# MAIN.net
KiCad netlist of a schematic drawn in Altium Designer
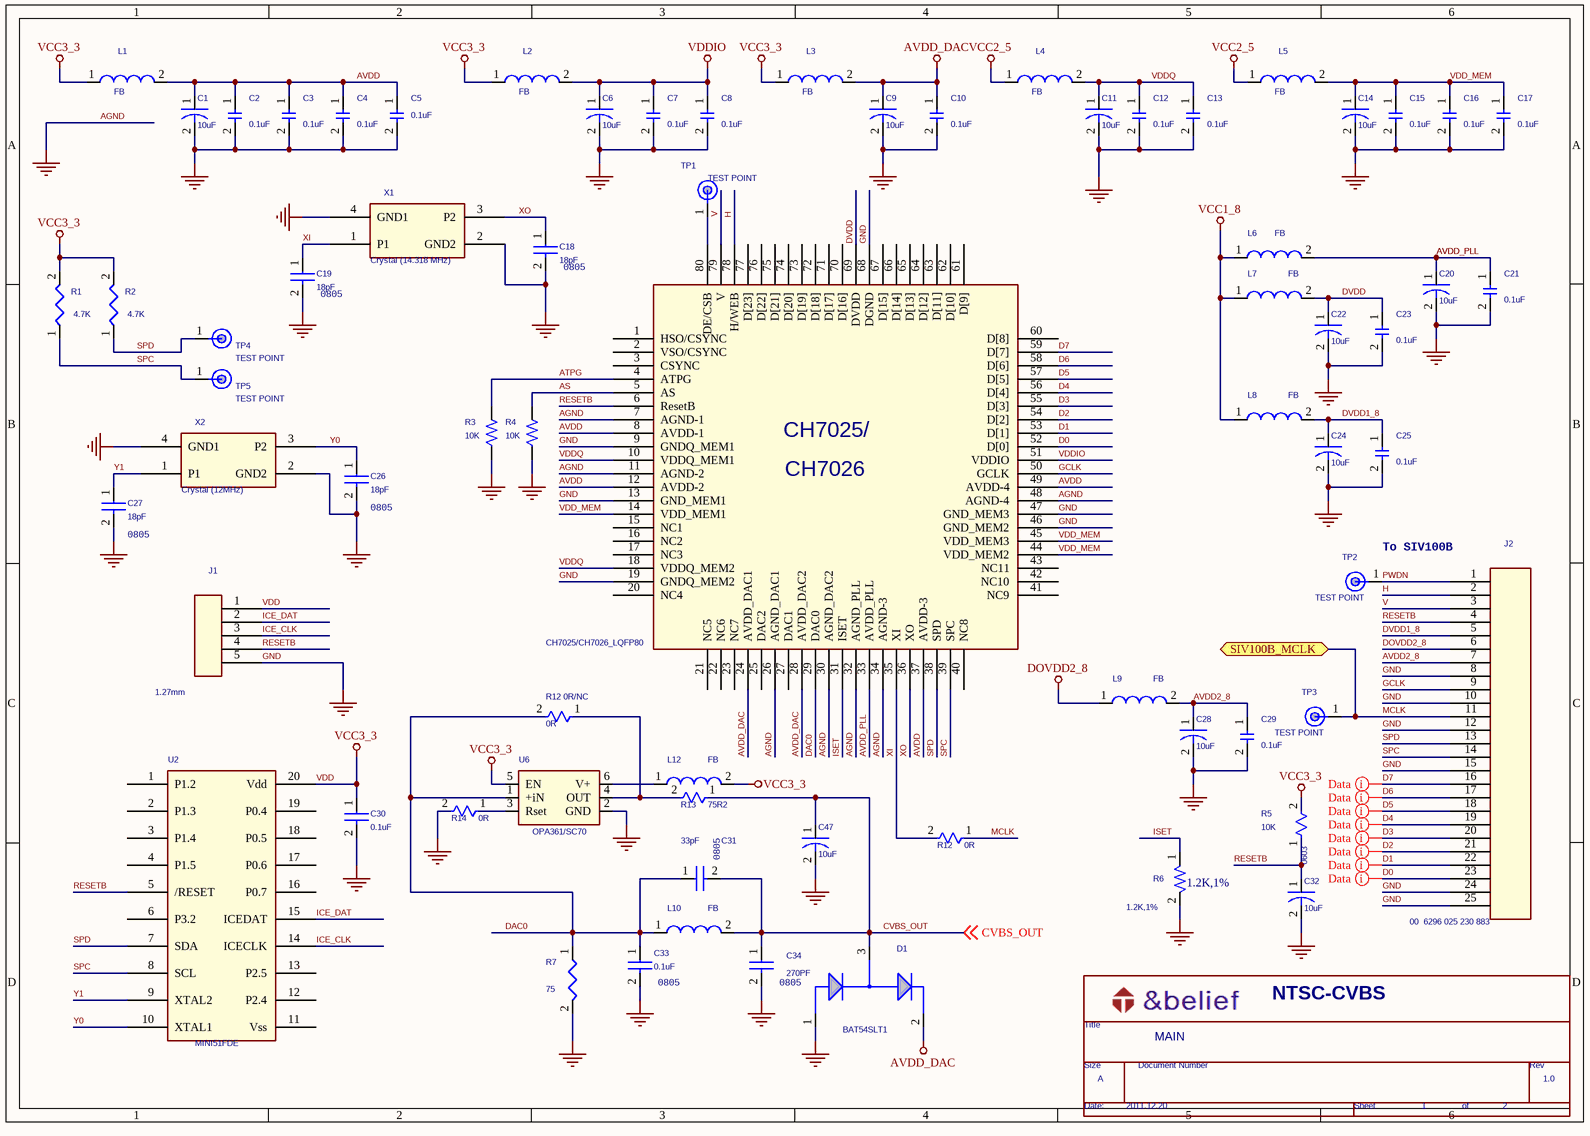
[diagram p0: MAIN.SchDoc]

(export (version "E")
  (design (tool "Eeschema 10.0.6"))
  (components
    (comp (ref "C1")
      (value "10uF")
      (footprint "CAPC1608X90N")
      (description "CAP - 10uF 16V TE Tant")
      (fields (field (name "MANUFACTURER PART NUM") "T491B106M016AS") (field (name "MANUFACTURER") "Kemet"))
      (libsource (lib "*") (part "PCAP_0"))
    )
    (comp (ref "C2")
      (value "0.1uF")
      (footprint "CAPC1005X55N")
      (fields (field (name "VOLTAGE") "CMAX"))
      (libsource (lib "*") (part "C_0"))
    )
    (comp (ref "C3")
      (value "0.1uF")
      (footprint "CAPC1005X55N")
      (fields (field (name "VOLTAGE") "CMAX"))
      (libsource (lib "*") (part "C_0"))
    )
    (comp (ref "C4")
      (value "0.1uF")
      (footprint "CAPC1005X55N")
      (fields (field (name "VOLTAGE") "CMAX"))
      (libsource (lib "*") (part "C_0"))
    )
    (comp (ref "C5")
      (value "0.1uF")
      (footprint "CAPC1005X55N")
      (fields (field (name "VOLTAGE") "CMAX"))
      (libsource (lib "*") (part "C_0"))
    )
    (comp (ref "C6")
      (value "10uF")
      (footprint "CAPC1608X90N")
      (description "CAP - 10uF 16V TE Tant")
      (fields (field (name "MANUFACTURER PART NUM") "T491B106M016AS") (field (name "MANUFACTURER") "Kemet"))
      (libsource (lib "*") (part "PCAP_0"))
    )
    (comp (ref "C7")
      (value "0.1uF")
      (footprint "CAPC1005X55N")
      (fields (field (name "VOLTAGE") "CMAX"))
      (libsource (lib "*") (part "C_0"))
    )
    (comp (ref "C8")
      (value "0.1uF")
      (footprint "CAPC1005X55N")
      (fields (field (name "VOLTAGE") "CMAX"))
      (libsource (lib "*") (part "C_0"))
    )
    (comp (ref "C9")
      (value "10uF")
      (footprint "CAPC1608X90N")
      (description "CAP - 10uF 16V TE Tant")
      (fields (field (name "MANUFACTURER PART NUM") "T491B106M016AS") (field (name "MANUFACTURER") "Kemet"))
      (libsource (lib "*") (part "PCAP_0"))
    )
    (comp (ref "C10")
      (value "0.1uF")
      (footprint "CAPC1005X55N")
      (fields (field (name "VOLTAGE") "CMAX"))
      (libsource (lib "*") (part "C_0"))
    )
    (comp (ref "C11")
      (value "10uF")
      (footprint "CAPC1608X90N")
      (description "CAP - 10uF 16V TE Tant")
      (fields (field (name "MANUFACTURER PART NUM") "T491B106M016AS") (field (name "MANUFACTURER") "Kemet"))
      (libsource (lib "*") (part "PCAP_0"))
    )
    (comp (ref "C12")
      (value "0.1uF")
      (footprint "CAPC1005X55N")
      (fields (field (name "VOLTAGE") "CMAX"))
      (libsource (lib "*") (part "C_0"))
    )
    (comp (ref "C13")
      (value "0.1uF")
      (footprint "CAPC1005X55N")
      (fields (field (name "VOLTAGE") "CMAX"))
      (libsource (lib "*") (part "C_0"))
    )
    (comp (ref "C14")
      (value "10uF")
      (footprint "CAPC1608X90N")
      (description "CAP - 10uF 16V TE Tant")
      (fields (field (name "MANUFACTURER PART NUM") "T491B106M016AS") (field (name "MANUFACTURER") "Kemet"))
      (libsource (lib "*") (part "PCAP_0"))
    )
    (comp (ref "C15")
      (value "0.1uF")
      (footprint "CAPC1005X55N")
      (fields (field (name "VOLTAGE") "CMAX"))
      (libsource (lib "*") (part "C_0"))
    )
    (comp (ref "C16")
      (value "0.1uF")
      (footprint "CAPC1005X55N")
      (fields (field (name "VOLTAGE") "CMAX"))
      (libsource (lib "*") (part "C_0"))
    )
    (comp (ref "C17")
      (value "0.1uF")
      (footprint "CAPC1005X55N")
      (fields (field (name "VOLTAGE") "CMAX"))
      (libsource (lib "*") (part "C_0"))
    )
    (comp (ref "C18")
      (value "18pF")
      (footprint "CAPC1005X55N")
      (fields (field (name "PART SHAPE") "0805"))
      (libsource (lib "*") (part "CAP"))
    )
    (comp (ref "C19")
      (value "18pF")
      (footprint "CAPC1005X55N")
      (fields (field (name "PART SHAPE") "0805"))
      (libsource (lib "*") (part "CAP"))
    )
    (comp (ref "C20")
      (value "10uF")
      (footprint "CAPC1608X90N")
      (description "CAP - 10uF 16V TE Tant")
      (fields (field (name "MANUFACTURER PART NUM") "T491B106M016AS") (field (name "MANUFACTURER") "Kemet"))
      (libsource (lib "*") (part "PCAP_0"))
    )
    (comp (ref "C21")
      (value "0.1uF")
      (footprint "CAPC1005X55N")
      (fields (field (name "VOLTAGE") "CMAX"))
      (libsource (lib "*") (part "C_0"))
    )
    (comp (ref "C22")
      (value "10uF")
      (footprint "CAPC1608X90N")
      (description "CAP - 10uF 16V TE Tant")
      (fields (field (name "MANUFATURER PART NUMBER") "T491B106M016AS") (field (name "MANUFACTURER") "Kemet"))
      (libsource (lib "*") (part "PCAP_0"))
    )
    (comp (ref "C23")
      (value "0.1uF")
      (footprint "CAPC1005X55N")
      (fields (field (name "VOLTAGE") "CMAX"))
      (libsource (lib "*") (part "C_0"))
    )
    (comp (ref "C24")
      (value "10uF")
      (footprint "CAPC1608X90N")
      (description "CAP - 10uF 16V TE Tant")
      (fields (field (name "MANUFACTURER PART NUM") "T491B106M016AS") (field (name "MANUFACTURER") "Kemet"))
      (libsource (lib "*") (part "PCAP_0"))
    )
    (comp (ref "C25")
      (value "0.1uF")
      (footprint "CAPC1005X55N")
      (fields (field (name "VOLTAGE") "CMAX"))
      (libsource (lib "*") (part "C_0"))
    )
    (comp (ref "C26")
      (value "18pF")
      (footprint "CAPC1005X55N")
      (fields (field (name "PART SHAPE") "0805"))
      (libsource (lib "*") (part "CAP"))
    )
    (comp (ref "C27")
      (value "18pF")
      (footprint "CAPC1005X55N")
      (fields (field (name "PART SHAPE") "0805"))
      (libsource (lib "*") (part "CAP"))
    )
    (comp (ref "C28")
      (value "10uF")
      (footprint "CAPC1608X90N")
      (description "CAP - 10uF 16V TE Tant")
      (fields (field (name "MANUFATURER PART NUMBER") "T491B106M016AS") (field (name "MANUFACTURER") "Kemet"))
      (libsource (lib "*") (part "PCAP_0"))
    )
    (comp (ref "C29")
      (value "0.1uF")
      (footprint "CAPC1005X55N")
      (fields (field (name "VOLTAGE") "CMAX"))
      (libsource (lib "*") (part "C_0"))
    )
    (comp (ref "C30") (value "0.1uF") (footprint "CAPC1005X55N") (libsource (lib "*") (part "CAP NP_3")))
    (comp (ref "C31")
      (value "33pF")
      (footprint "CAPC1005X55N")
      (fields (field (name "PART SHAPE") "0805"))
      (libsource (lib "*") (part "CAP"))
    )
    (comp (ref "C32")
      (value "10uF")
      (footprint "CAPC1608X90N")
      (description "CAP - 10uF 16V TE Tant")
      (fields (field (name "MANUFATURER PART NUMBER") "T491B106M016AS") (field (name "MANUFACTURER") "Kemet"))
      (libsource (lib "*") (part "PCAP_0"))
    )
    (comp (ref "C33")
      (value "0.1uF")
      (footprint "CAPC1005X55N")
      (fields (field (name "PART SHAPE") "0805"))
      (libsource (lib "*") (part "CAP"))
    )
    (comp (ref "C34")
      (value "270PF")
      (footprint "CAPC1005X55N")
      (fields (field (name "PART SHAPE") "0805"))
      (libsource (lib "*") (part "CAP"))
    )
    (comp (ref "C47")
      (value "10uF")
      (footprint "CAPC1608X90N")
      (description "CAP - 10uF 16V TE Tant")
      (fields (field (name "MANUFATURER PART NUMBER") "T491B106M016AS") (field (name "MANUFACTURER") "Kemet"))
      (libsource (lib "*") (part "PCAP_0"))
    )
    (comp (ref "D1")
      (value "BAT54SLT1")
      (footprint "SOT23-3")
      (libsource (lib "*") (part "DIODE DUAL SERIES SOT23"))
    )
    (comp (ref "J1") (value "1.27mm") (footprint "JP 1.27mm") (libsource (lib "*") (part "CON5_Dup1")))
    (comp (ref "J2")
      (value "00  6296 025 230 883")
      (footprint "FPC ASSY 0.3MM")
      (libsource (lib "*") (part "CON25"))
    )
    (comp (ref "L1") (value "FB") (footprint "INDC1005N") (libsource (lib "*") (part "INDUCTOR")))
    (comp (ref "L2") (value "FB") (footprint "INDC1005N") (libsource (lib "*") (part "INDUCTOR")))
    (comp (ref "L3") (value "FB") (footprint "INDC1005N") (libsource (lib "*") (part "INDUCTOR")))
    (comp (ref "L4") (value "FB") (footprint "INDC1005N") (libsource (lib "*") (part "INDUCTOR")))
    (comp (ref "L5") (value "FB") (footprint "INDC1005N") (libsource (lib "*") (part "INDUCTOR")))
    (comp (ref "L6") (value "FB") (footprint "INDC1005N") (libsource (lib "*") (part "INDUCTOR")))
    (comp (ref "L7") (value "FB") (footprint "INDC1005N") (libsource (lib "*") (part "INDUCTOR")))
    (comp (ref "L8") (value "FB") (footprint "INDC1005N") (libsource (lib "*") (part "INDUCTOR")))
    (comp (ref "L9") (value "FB") (footprint "INDC1005N") (libsource (lib "*") (part "INDUCTOR")))
    (comp (ref "L10") (value "FB") (footprint "INDC1608N") (libsource (lib "*") (part "INDUCTOR")))
    (comp (ref "L12") (value "FB") (footprint "INDC1005N") (libsource (lib "*") (part "INDUCTOR")))
    (comp (ref "R1") (value "4.7K") (footprint "RESC1005X40N") (libsource (lib "*") (part "RESISTOR")))
    (comp (ref "R2") (value "4.7K") (footprint "RESC1005X40N") (libsource (lib "*") (part "RESISTOR")))
    (comp (ref "R3")
      (value "10K")
      (footprint "RESC1005X40N")
      (fields (field (name "POWER") "RMAX") (field (name "VOLTAGE") "RVMAX"))
      (libsource (lib "*") (part "R"))
    )
    (comp (ref "R4")
      (value "10K")
      (footprint "RESC1005X40N")
      (fields (field (name "POWER") "RMAX") (field (name "VOLTAGE") "RVMAX"))
      (libsource (lib "*") (part "R"))
    )
    (comp (ref "R5")
      (value "10K")
      (footprint "RESC1005X40N")
      (description "0R,1/10W,5%,0603")
      (fields (field (name "TOLERANCE") "∮5%") (field (name "SIZE") "0603"))
      (libsource (lib "*") (part "0R,1/10W,5%,0603_9"))
    )
    (comp (ref "R6")
      (value "1.2K,1%")
      (footprint "RESC1005X40N")
      (fields
        (field (name "POWER") "RMAX")
        (field (name "VOLTAGE") "RVMAX")
        (field (name "ALTIUM_VALUE") "1.2K,1%")
      )
      (libsource (lib "*") (part "R_4"))
    )
    (comp (ref "R7") (value "75") (footprint "RESC1005X40N") (libsource (lib "*") (part "RESISTOR")))
    (comp (ref "R12")
      (value "0R")
      (footprint "RESC1005X40N")
      (description "0R,1/10W,5%,0603")
      (fields (field (name "TOLERANCE") "∮5%"))
      (libsource (lib "*") (part "0R,1/10W,5%,0603_9"))
    )
    (comp (ref "R12 0R/NC")
      (value "0R")
      (footprint "RESC1005X40N")
      (description "0R,1/10W,5%,0603")
      (fields (field (name "TOLERANCE") "∮5%"))
      (libsource (lib "*") (part "0R,1/10W,5%,0603_9"))
    )
    (comp (ref "R13")
      (value "75R2")
      (footprint "RESC1005X40N")
      (description "0R,1/10W,5%,0603")
      (fields (field (name "TOLERANCE") "∮5%"))
      (libsource (lib "*") (part "0R,1/10W,5%,0603_9"))
    )
    (comp (ref "R14")
      (value "0R")
      (footprint "RESC1005X40N")
      (description "0R,1/10W,5%,0603")
      (fields (field (name "TOLERANCE") "∮5%"))
      (libsource (lib "*") (part "0R,1/10W,5%,0603_9"))
    )
    (comp (ref "TP1") (value "TEST POINT") (footprint "TP-R20") (libsource (lib "*") (part "Test Point_0")))
    (comp (ref "TP2") (value "TEST POINT") (footprint "TP-R20") (libsource (lib "*") (part "Test Point_1")))
    (comp (ref "TP3") (value "TEST POINT") (footprint "TP-R20") (libsource (lib "*") (part "Test Point_2")))
    (comp (ref "TP4") (value "TEST POINT") (footprint "TP-R20") (libsource (lib "*") (part "Test Point_0")))
    (comp (ref "TP5") (value "TEST POINT") (footprint "TP-R20") (libsource (lib "*") (part "Test Point_0")))
    (comp (ref "U1")
      (value "CH7025/CH7026_LQFP80")
      (footprint "TQFP80_N")
      (libsource (lib "*") (part "CH7025_LQFP80_0"))
    )
    (comp (ref "U2")
      (value "MINI51FDE")
      (footprint "TSSOP65P640X120-20N")
      (libsource (lib "*") (part "IC TvDecoder TI TVP5150 QFP32_2"))
    )
    (comp (ref "U6")
      (value "OPA361/SC70")
      (footprint "SC07")
      (libsource (lib "*") (part "IC DC/DC RT8258 SOT26_0"))
    )
    (comp (ref "X1")
      (value "Crystal (14.318 MHz)")
      (footprint "XTAL-4pin-3225")
      (libsource (lib "*") (part "535-9118-1-ND_0"))
    )
    (comp (ref "X2")
      (value "Crystal (12MHz)")
      (footprint "XTAL-4pin-3225")
      (libsource (lib "*") (part "535-9118-1-ND_1"))
    )
  )
  (nets
    (net (code "1") (name "/AS") (class "Default")
      (node (ref "R4") (pin "2") (pinfunction "2_2") (pintype "passive"))
      (node (ref "U1") (pin "5") (pinfunction "AS_5") (pintype "passive"))
    )
    (net (code "2") (name "/ATPG") (class "Default")
      (node (ref "R3") (pin "2") (pinfunction "2_2") (pintype "passive"))
      (node (ref "U1") (pin "4") (pinfunction "ATPG_4") (pintype "passive"))
    )
    (net (code "3") (name "/AVDD") (class "Default")
      (node (ref "C1") (pin "1") (pinfunction "1_1") (pintype "passive"))
      (node (ref "C2") (pin "1") (pinfunction "1_1") (pintype "passive"))
      (node (ref "C3") (pin "1") (pinfunction "1_1") (pintype "passive"))
      (node (ref "C4") (pin "1") (pinfunction "1_1") (pintype "passive"))
      (node (ref "C5") (pin "1") (pinfunction "1_1") (pintype "passive"))
      (node (ref "L1") (pin "2") (pinfunction "2_2") (pintype "passive"))
      (node (ref "U1") (pin "12") (pinfunction "AVDD-2_12") (pintype "passive"))
      (node (ref "U1") (pin "37") (pinfunction "AVDD-3_37") (pintype "passive"))
      (node (ref "U1") (pin "49") (pinfunction "AVDD-4_49") (pintype "passive"))
      (node (ref "U1") (pin "8") (pinfunction "AVDD-1_8") (pintype "passive"))
    )
    (net (code "4") (name "/AVDD2_8") (class "Default")
      (node (ref "C28") (pin "1") (pinfunction "1_1") (pintype "passive"))
      (node (ref "C29") (pin "1") (pinfunction "1_1") (pintype "passive"))
      (node (ref "J2") (pin "7") (pinfunction "7_7") (pintype "passive"))
      (node (ref "L9") (pin "2") (pinfunction "2_2") (pintype "passive"))
    )
    (net (code "5") (name "/AVDD_PLL") (class "Default")
      (node (ref "C20") (pin "1") (pinfunction "1_1") (pintype "passive"))
      (node (ref "C21") (pin "1") (pinfunction "1_1") (pintype "passive"))
      (node (ref "L6") (pin "2") (pinfunction "2_2") (pintype "passive"))
      (node (ref "U1") (pin "33") (pinfunction "AVDD_PLL_33") (pintype "passive"))
    )
    (net (code "6") (name "/D0") (class "Default")
      (node (ref "J2") (pin "23") (pinfunction "23_23") (pintype "passive"))
      (node (ref "U1") (pin "52") (pinfunction "D[0]_52") (pintype "passive"))
    )
    (net (code "7") (name "/D1") (class "Default")
      (node (ref "J2") (pin "22") (pinfunction "22_22") (pintype "passive"))
      (node (ref "U1") (pin "53") (pinfunction "D[1]_53") (pintype "passive"))
    )
    (net (code "8") (name "/D2") (class "Default")
      (node (ref "J2") (pin "21") (pinfunction "21_21") (pintype "passive"))
      (node (ref "U1") (pin "54") (pinfunction "D[2]_54") (pintype "passive"))
    )
    (net (code "9") (name "/D3") (class "Default")
      (node (ref "J2") (pin "20") (pinfunction "20_20") (pintype "passive"))
      (node (ref "U1") (pin "55") (pinfunction "D[3]_55") (pintype "passive"))
    )
    (net (code "10") (name "/D4") (class "Default")
      (node (ref "J2") (pin "19") (pinfunction "19_19") (pintype "passive"))
      (node (ref "U1") (pin "56") (pinfunction "D[4]_56") (pintype "passive"))
    )
    (net (code "11") (name "/D5") (class "Default")
      (node (ref "J2") (pin "18") (pinfunction "18_18") (pintype "passive"))
      (node (ref "U1") (pin "57") (pinfunction "D[5]_57") (pintype "passive"))
    )
    (net (code "12") (name "/D6") (class "Default")
      (node (ref "J2") (pin "17") (pinfunction "17_17") (pintype "passive"))
      (node (ref "U1") (pin "58") (pinfunction "D[6]_58") (pintype "passive"))
    )
    (net (code "13") (name "/D7") (class "Default")
      (node (ref "J2") (pin "16") (pinfunction "16_16") (pintype "passive"))
      (node (ref "U1") (pin "59") (pinfunction "D[7]_59") (pintype "passive"))
    )
    (net (code "14") (name "/DAC0") (class "Default")
      (node (ref "C31") (pin "1") (pinfunction "1_1") (pintype "passive"))
      (node (ref "C33") (pin "1") (pinfunction "1_1") (pintype "passive"))
      (node (ref "L10") (pin "1") (pinfunction "1_1") (pintype "passive"))
      (node (ref "R12 0R/NC") (pin "2") (pinfunction "2_2") (pintype "passive"))
      (node (ref "R7") (pin "1") (pinfunction "1_1") (pintype "passive"))
      (node (ref "U1") (pin "29") (pinfunction "DAC0_29") (pintype "passive"))
      (node (ref "U6") (pin "1") (pinfunction "+iN_1") (pintype "passive"))
    )
    (net (code "15") (name "/DVDD") (class "Default")
      (node (ref "C22") (pin "1") (pinfunction "1_1") (pintype "passive"))
      (node (ref "C23") (pin "1") (pinfunction "1_1") (pintype "passive"))
      (node (ref "L7") (pin "2") (pinfunction "2_2") (pintype "passive"))
      (node (ref "U1") (pin "69") (pinfunction "DVDD_69") (pintype "passive"))
    )
    (net (code "16") (name "/DVDD1_8") (class "Default")
      (node (ref "C24") (pin "1") (pinfunction "1_1") (pintype "passive"))
      (node (ref "C25") (pin "1") (pinfunction "1_1") (pintype "passive"))
      (node (ref "J2") (pin "5") (pinfunction "5_5") (pintype "passive"))
      (node (ref "L8") (pin "2") (pinfunction "2_2") (pintype "passive"))
    )
    (net (code "17") (name "/GCLK") (class "Default")
      (node (ref "J2") (pin "9") (pinfunction "9_9") (pintype "passive"))
      (node (ref "U1") (pin "50") (pinfunction "GCLK_50") (pintype "passive"))
    )
    (net (code "18") (name "/H") (class "Default")
      (node (ref "J2") (pin "2") (pinfunction "2_2") (pintype "passive"))
      (node (ref "U1") (pin "78") (pinfunction "H/WEB_78") (pintype "passive"))
    )
    (net (code "19") (name "/ICE_CLK") (class "Default")
      (node (ref "J1") (pin "3") (pinfunction "3_3") (pintype "passive"))
      (node (ref "U2") (pin "14") (pinfunction "ICECLK_14") (pintype "passive"))
    )
    (net (code "20") (name "/ICE_DAT") (class "Default")
      (node (ref "J1") (pin "2") (pinfunction "2_2") (pintype "passive"))
      (node (ref "U2") (pin "15") (pinfunction "ICEDAT_15") (pintype "passive"))
    )
    (net (code "21") (name "/ISET") (class "Default")
      (node (ref "R6") (pin "1") (pinfunction "1_1") (pintype "passive"))
      (node (ref "U1") (pin "31") (pinfunction "ISET_31") (pintype "passive"))
    )
    (net (code "22") (name "/MCLK") (class "Default")
      (node (ref "J2") (pin "11") (pinfunction "11_11") (pintype "passive"))
      (node (ref "R12") (pin "1") (pinfunction "1_1") (pintype "passive"))
      (node (ref "TP3") (pin "1") (pinfunction "1_1") (pintype "passive"))
    )
    (net (code "23") (name "/PWDN") (class "Default")
      (node (ref "J2") (pin "1") (pinfunction "1_1") (pintype "passive"))
      (node (ref "TP2") (pin "1") (pinfunction "1_1") (pintype "passive"))
    )
    (net (code "24") (name "/RESETB") (class "Default")
      (node (ref "C32") (pin "1") (pinfunction "1_1") (pintype "passive"))
      (node (ref "J1") (pin "4") (pinfunction "4_4") (pintype "passive"))
      (node (ref "J2") (pin "4") (pinfunction "4_4") (pintype "passive"))
      (node (ref "R5") (pin "1") (pinfunction "1_1") (pintype "passive"))
      (node (ref "U1") (pin "6") (pinfunction "ResetB_6") (pintype "passive"))
      (node (ref "U2") (pin "5") (pinfunction "/RESET_5") (pintype "passive"))
    )
    (net (code "25") (name "/SPC") (class "Default")
      (node (ref "J2") (pin "14") (pinfunction "14_14") (pintype "passive"))
      (node (ref "R1") (pin "1") (pinfunction "1_1") (pintype "passive"))
      (node (ref "TP5") (pin "1") (pinfunction "1_1") (pintype "passive"))
      (node (ref "U1") (pin "39") (pinfunction "SPC_39") (pintype "passive"))
      (node (ref "U2") (pin "8") (pinfunction "SCL_8") (pintype "passive"))
    )
    (net (code "26") (name "/SPD") (class "Default")
      (node (ref "J2") (pin "13") (pinfunction "13_13") (pintype "passive"))
      (node (ref "R2") (pin "1") (pinfunction "1_1") (pintype "passive"))
      (node (ref "TP4") (pin "1") (pinfunction "1_1") (pintype "passive"))
      (node (ref "U1") (pin "38") (pinfunction "SPD_38") (pintype "passive"))
      (node (ref "U2") (pin "7") (pinfunction "SDA_7") (pintype "passive"))
    )
    (net (code "27") (name "/V") (class "Default")
      (node (ref "J2") (pin "3") (pinfunction "3_3") (pintype "passive"))
      (node (ref "U1") (pin "79") (pinfunction "V_79") (pintype "passive"))
    )
    (net (code "28") (name "/VDDQ") (class "Default")
      (node (ref "C11") (pin "1") (pinfunction "1_1") (pintype "passive"))
      (node (ref "C12") (pin "1") (pinfunction "1_1") (pintype "passive"))
      (node (ref "C13") (pin "1") (pinfunction "1_1") (pintype "passive"))
      (node (ref "L4") (pin "2") (pinfunction "2_2") (pintype "passive"))
      (node (ref "U1") (pin "10") (pinfunction "VDDQ_MEM1_10") (pintype "passive"))
      (node (ref "U1") (pin "18") (pinfunction "VDDQ_MEM2_18") (pintype "passive"))
    )
    (net (code "29") (name "/VDD_MEM") (class "Default")
      (node (ref "C14") (pin "1") (pinfunction "1_1") (pintype "passive"))
      (node (ref "C15") (pin "1") (pinfunction "1_1") (pintype "passive"))
      (node (ref "C16") (pin "1") (pinfunction "1_1") (pintype "passive"))
      (node (ref "C17") (pin "1") (pinfunction "1_1") (pintype "passive"))
      (node (ref "L5") (pin "2") (pinfunction "2_2") (pintype "passive"))
      (node (ref "U1") (pin "14") (pinfunction "VDD_MEM1_14") (pintype "passive"))
      (node (ref "U1") (pin "44") (pinfunction "VDD_MEM2_44") (pintype "passive"))
      (node (ref "U1") (pin "45") (pinfunction "VDD_MEM3_45") (pintype "passive"))
    )
    (net (code "30") (name "/XI") (class "Default")
      (node (ref "C19") (pin "1") (pinfunction "1_1") (pintype "passive"))
      (node (ref "R12") (pin "2") (pinfunction "2_2") (pintype "passive"))
      (node (ref "U1") (pin "35") (pinfunction "XI_35") (pintype "passive"))
      (node (ref "X1") (pin "1") (pinfunction "P1_1") (pintype "passive"))
    )
    (net (code "31") (name "/XO") (class "Default")
      (node (ref "C18") (pin "1") (pinfunction "1_1") (pintype "passive"))
      (node (ref "U1") (pin "36") (pinfunction "XO_36") (pintype "passive"))
      (node (ref "X1") (pin "3") (pinfunction "P2_3") (pintype "passive"))
    )
    (net (code "32") (name "/Y0") (class "Default")
      (node (ref "C26") (pin "1") (pinfunction "1_1") (pintype "passive"))
      (node (ref "U2") (pin "10") (pinfunction "XTAL1_10") (pintype "passive"))
      (node (ref "X2") (pin "3") (pinfunction "P2_3") (pintype "passive"))
    )
    (net (code "33") (name "/Y1") (class "Default")
      (node (ref "C27") (pin "1") (pinfunction "1_1") (pintype "passive"))
      (node (ref "U2") (pin "9") (pinfunction "XTAL2_9") (pintype "passive"))
      (node (ref "X2") (pin "1") (pinfunction "P1_1") (pintype "passive"))
    )
    (net (code "34") (name "AVDD_DAC") (class "Default")
      (node (ref "C10") (pin "1") (pinfunction "1_1") (pintype "passive"))
      (node (ref "C9") (pin "1") (pinfunction "1_1") (pintype "passive"))
      (node (ref "D1") (pin "2") (pinfunction "VDD_2") (pintype "passive"))
      (node (ref "L3") (pin "2") (pinfunction "2_2") (pintype "passive"))
      (node (ref "U1") (pin "24") (pinfunction "AVDD_DAC1_24") (pintype "passive"))
      (node (ref "U1") (pin "28") (pinfunction "AVDD_DAC2_28") (pintype "passive"))
    )
    (net (code "35") (name "CVBS_OUT") (class "Default")
      (node (ref "C31") (pin "2") (pinfunction "2_2") (pintype "passive"))
      (node (ref "C34") (pin "1") (pinfunction "1_1") (pintype "passive"))
      (node (ref "C47") (pin "1") (pinfunction "1_1") (pintype "passive"))
      (node (ref "D1") (pin "3") (pinfunction "SIGNAL_3") (pintype "passive"))
      (node (ref "L10") (pin "2") (pinfunction "2_2") (pintype "passive"))
      (node (ref "R13") (pin "1") (pinfunction "1_1") (pintype "passive"))
    )
    (net (code "36") (name "DOVDD2_8") (class "Default")
      (node (ref "J2") (pin "6") (pinfunction "6_6") (pintype "passive"))
      (node (ref "L9") (pin "1") (pinfunction "1_1") (pintype "passive"))
    )
    (net (code "37") (name "GND") (class "Default")
      (node (ref "C1") (pin "2") (pinfunction "2_2") (pintype "passive"))
      (node (ref "C10") (pin "2") (pinfunction "2_2") (pintype "passive"))
      (node (ref "C11") (pin "2") (pinfunction "2_2") (pintype "passive"))
      (node (ref "C12") (pin "2") (pinfunction "2_2") (pintype "passive"))
      (node (ref "C13") (pin "2") (pinfunction "2_2") (pintype "passive"))
      (node (ref "C14") (pin "2") (pinfunction "2_2") (pintype "passive"))
      (node (ref "C15") (pin "2") (pinfunction "2_2") (pintype "passive"))
      (node (ref "C16") (pin "2") (pinfunction "2_2") (pintype "passive"))
      (node (ref "C17") (pin "2") (pinfunction "2_2") (pintype "passive"))
      (node (ref "C18") (pin "2") (pinfunction "2_2") (pintype "passive"))
      (node (ref "C19") (pin "2") (pinfunction "2_2") (pintype "passive"))
      (node (ref "C2") (pin "2") (pinfunction "2_2") (pintype "passive"))
      (node (ref "C20") (pin "2") (pinfunction "2_2") (pintype "passive"))
      (node (ref "C21") (pin "2") (pinfunction "2_2") (pintype "passive"))
      (node (ref "C22") (pin "2") (pinfunction "2_2") (pintype "passive"))
      (node (ref "C23") (pin "2") (pinfunction "2_2") (pintype "passive"))
      (node (ref "C24") (pin "2") (pinfunction "2_2") (pintype "passive"))
      (node (ref "C25") (pin "2") (pinfunction "2_2") (pintype "passive"))
      (node (ref "C26") (pin "2") (pinfunction "2_2") (pintype "passive"))
      (node (ref "C27") (pin "2") (pinfunction "2_2") (pintype "passive"))
      (node (ref "C28") (pin "2") (pinfunction "2_2") (pintype "passive"))
      (node (ref "C29") (pin "2") (pinfunction "2_2") (pintype "passive"))
      (node (ref "C3") (pin "2") (pinfunction "2_2") (pintype "passive"))
      (node (ref "C30") (pin "2") (pinfunction "2_2") (pintype "passive"))
      (node (ref "C32") (pin "2") (pinfunction "2_2") (pintype "passive"))
      (node (ref "C33") (pin "2") (pinfunction "2_2") (pintype "passive"))
      (node (ref "C34") (pin "2") (pinfunction "2_2") (pintype "passive"))
      (node (ref "C4") (pin "2") (pinfunction "2_2") (pintype "passive"))
      (node (ref "C47") (pin "2") (pinfunction "2_2") (pintype "passive"))
      (node (ref "C5") (pin "2") (pinfunction "2_2") (pintype "passive"))
      (node (ref "C6") (pin "2") (pinfunction "2_2") (pintype "passive"))
      (node (ref "C7") (pin "2") (pinfunction "2_2") (pintype "passive"))
      (node (ref "C8") (pin "2") (pinfunction "2_2") (pintype "passive"))
      (node (ref "C9") (pin "2") (pinfunction "2_2") (pintype "passive"))
      (node (ref "D1") (pin "1") (pinfunction "GND_1") (pintype "passive"))
      (node (ref "J1") (pin "5") (pinfunction "5_5") (pintype "passive"))
      (node (ref "J2") (pin "10") (pinfunction "10_10") (pintype "passive"))
      (node (ref "J2") (pin "12") (pinfunction "12_12") (pintype "passive"))
      (node (ref "J2") (pin "15") (pinfunction "15_15") (pintype "passive"))
      (node (ref "J2") (pin "24") (pinfunction "24_24") (pintype "passive"))
      (node (ref "J2") (pin "25") (pinfunction "25_25") (pintype "passive"))
      (node (ref "J2") (pin "8") (pinfunction "8_8") (pintype "passive"))
      (node (ref "R14") (pin "2") (pinfunction "2_2") (pintype "passive"))
      (node (ref "R3") (pin "1") (pinfunction "1_1") (pintype "passive"))
      (node (ref "R4") (pin "1") (pinfunction "1_1") (pintype "passive"))
      (node (ref "R6") (pin "2") (pinfunction "2_2") (pintype "passive"))
      (node (ref "R7") (pin "2") (pinfunction "2_2") (pintype "passive"))
      (node (ref "U1") (pin "11") (pinfunction "AGND-2_11") (pintype "passive"))
      (node (ref "U1") (pin "13") (pinfunction "GND_MEM1_13") (pintype "passive"))
      (node (ref "U1") (pin "19") (pinfunction "GNDQ_MEM2_19") (pintype "passive"))
      (node (ref "U1") (pin "26") (pinfunction "AGND_DAC1_26") (pintype "passive"))
      (node (ref "U1") (pin "30") (pinfunction "AGND_DAC2_30") (pintype "passive"))
      (node (ref "U1") (pin "32") (pinfunction "AGND_PLL_32") (pintype "passive"))
      (node (ref "U1") (pin "34") (pinfunction "AGND-3_34") (pintype "passive"))
      (node (ref "U1") (pin "46") (pinfunction "GND_MEM2_46") (pintype "passive"))
      (node (ref "U1") (pin "47") (pinfunction "GND_MEM3_47") (pintype "passive"))
      (node (ref "U1") (pin "48") (pinfunction "AGND-4_48") (pintype "passive"))
      (node (ref "U1") (pin "68") (pinfunction "DGND_68") (pintype "passive"))
      (node (ref "U1") (pin "7") (pinfunction "AGND-1_7") (pintype "passive"))
      (node (ref "U1") (pin "9") (pinfunction "GNDQ_MEM1_9") (pintype "passive"))
      (node (ref "U6") (pin "2") (pinfunction "GND_2") (pintype "passive"))
      (node (ref "X1") (pin "2") (pinfunction "GND2_2") (pintype "passive"))
      (node (ref "X1") (pin "4") (pinfunction "GND1_4") (pintype "passive"))
      (node (ref "X2") (pin "2") (pinfunction "GND2_2") (pintype "passive"))
      (node (ref "X2") (pin "4") (pinfunction "GND1_4") (pintype "passive"))
    )
    (net (code "38") (name "Net-(U1-DE{slash}CSB)") (class "Default")
      (node (ref "TP1") (pin "1") (pinfunction "1_1") (pintype "passive"))
      (node (ref "U1") (pin "80") (pinfunction "DE/CSB_80") (pintype "passive"))
    )
    (net (code "39") (name "Net-(U6-OUT)") (class "Default")
      (node (ref "R12 0R/NC") (pin "1") (pinfunction "1_1") (pintype "passive"))
      (node (ref "R13") (pin "2") (pinfunction "2_2") (pintype "passive"))
      (node (ref "U6") (pin "4") (pinfunction "OUT_4") (pintype "passive"))
    )
    (net (code "40") (name "Net-(U6-Rset)") (class "Default")
      (node (ref "R14") (pin "1") (pinfunction "1_1") (pintype "passive"))
      (node (ref "U6") (pin "3") (pinfunction "Rset_3") (pintype "passive"))
    )
    (net (code "41") (name "Net-(U6-V+)") (class "Default")
      (node (ref "L12") (pin "1") (pinfunction "1_1") (pintype "passive"))
      (node (ref "U6") (pin "6") (pinfunction "V+_6") (pintype "passive"))
    )
    (net (code "42") (name "VCC1_8") (class "Default")
      (node (ref "L6") (pin "1") (pinfunction "1_1") (pintype "passive"))
      (node (ref "L7") (pin "1") (pinfunction "1_1") (pintype "passive"))
      (node (ref "L8") (pin "1") (pinfunction "1_1") (pintype "passive"))
    )
    (net (code "43") (name "VCC2_5") (class "Default")
      (node (ref "L4") (pin "1") (pinfunction "1_1") (pintype "passive"))
      (node (ref "L5") (pin "1") (pinfunction "1_1") (pintype "passive"))
    )
    (net (code "44") (name "VCC3_3") (class "Default")
      (node (ref "C30") (pin "1") (pinfunction "1_1") (pintype "passive"))
      (node (ref "J1") (pin "1") (pinfunction "1_1") (pintype "passive"))
      (node (ref "L1") (pin "1") (pinfunction "1_1") (pintype "passive"))
      (node (ref "L12") (pin "2") (pinfunction "2_2") (pintype "passive"))
      (node (ref "L2") (pin "1") (pinfunction "1_1") (pintype "passive"))
      (node (ref "L3") (pin "1") (pinfunction "1_1") (pintype "passive"))
      (node (ref "R1") (pin "2") (pinfunction "2_2") (pintype "passive"))
      (node (ref "R2") (pin "2") (pinfunction "2_2") (pintype "passive"))
      (node (ref "R5") (pin "2") (pinfunction "2_2") (pintype "passive"))
      (node (ref "U2") (pin "20") (pinfunction "Vdd_20") (pintype "passive"))
      (node (ref "U6") (pin "5") (pinfunction "EN_5") (pintype "passive"))
    )
    (net (code "45") (name "VDDIO") (class "Default")
      (node (ref "C6") (pin "1") (pinfunction "1_1") (pintype "passive"))
      (node (ref "C7") (pin "1") (pinfunction "1_1") (pintype "passive"))
      (node (ref "C8") (pin "1") (pinfunction "1_1") (pintype "passive"))
      (node (ref "L2") (pin "2") (pinfunction "2_2") (pintype "passive"))
      (node (ref "U1") (pin "51") (pinfunction "VDDIO_51") (pintype "passive"))
    )
    (net (code "46") (name "unconnected-(U1-CSYNC-Pad3)") (class "Default")
      (node (ref "U1") (pin "3") (pinfunction "CSYNC_3") (pintype "passive"))
    )
    (net (code "47") (name "unconnected-(U1-DAC1-Pad27)") (class "Default")
      (node (ref "U1") (pin "27") (pinfunction "DAC1_27") (pintype "passive"))
    )
    (net (code "48") (name "unconnected-(U1-DAC2-Pad25)") (class "Default")
      (node (ref "U1") (pin "25") (pinfunction "DAC2_25") (pintype "passive"))
    )
    (net (code "49") (name "unconnected-(U1-D[8]-Pad60)") (class "Default")
      (node (ref "U1") (pin "60") (pinfunction "D[8]_60") (pintype "passive"))
    )
    (net (code "50") (name "unconnected-(U1-D[9]-Pad61)") (class "Default")
      (node (ref "U1") (pin "61") (pinfunction "D[9]_61") (pintype "passive"))
    )
    (net (code "51") (name "unconnected-(U1-D[10]-Pad62)") (class "Default")
      (node (ref "U1") (pin "62") (pinfunction "D[10]_62") (pintype "passive"))
    )
    (net (code "52") (name "unconnected-(U1-D[11]-Pad63)") (class "Default")
      (node (ref "U1") (pin "63") (pinfunction "D[11]_63") (pintype "passive"))
    )
    (net (code "53") (name "unconnected-(U1-D[12]-Pad64)") (class "Default")
      (node (ref "U1") (pin "64") (pinfunction "D[12]_64") (pintype "passive"))
    )
    (net (code "54") (name "unconnected-(U1-D[13]-Pad65)") (class "Default")
      (node (ref "U1") (pin "65") (pinfunction "D[13]_65") (pintype "passive"))
    )
    (net (code "55") (name "unconnected-(U1-D[14]-Pad66)") (class "Default")
      (node (ref "U1") (pin "66") (pinfunction "D[14]_66") (pintype "passive"))
    )
    (net (code "56") (name "unconnected-(U1-D[15]-Pad67)") (class "Default")
      (node (ref "U1") (pin "67") (pinfunction "D[15]_67") (pintype "passive"))
    )
    (net (code "57") (name "unconnected-(U1-D[16]-Pad70)") (class "Default")
      (node (ref "U1") (pin "70") (pinfunction "D[16]_70") (pintype "passive"))
    )
    (net (code "58") (name "unconnected-(U1-D[17]-Pad71)") (class "Default")
      (node (ref "U1") (pin "71") (pinfunction "D[17]_71") (pintype "passive"))
    )
    (net (code "59") (name "unconnected-(U1-D[18]-Pad72)") (class "Default")
      (node (ref "U1") (pin "72") (pinfunction "D[18]_72") (pintype "passive"))
    )
    (net (code "60") (name "unconnected-(U1-D[19]-Pad73)") (class "Default")
      (node (ref "U1") (pin "73") (pinfunction "D[19]_73") (pintype "passive"))
    )
    (net (code "61") (name "unconnected-(U1-D[20]-Pad74)") (class "Default")
      (node (ref "U1") (pin "74") (pinfunction "D[20]_74") (pintype "passive"))
    )
    (net (code "62") (name "unconnected-(U1-D[21]-Pad75)") (class "Default")
      (node (ref "U1") (pin "75") (pinfunction "D[21]_75") (pintype "passive"))
    )
    (net (code "63") (name "unconnected-(U1-D[22]-Pad76)") (class "Default")
      (node (ref "U1") (pin "76") (pinfunction "D[22]_76") (pintype "passive"))
    )
    (net (code "64") (name "unconnected-(U1-D[23]-Pad77)") (class "Default")
      (node (ref "U1") (pin "77") (pinfunction "D[23]_77") (pintype "passive"))
    )
    (net (code "65") (name "unconnected-(U1-HSO{slash}CSYNC-Pad1)") (class "Default")
      (node (ref "U1") (pin "1") (pinfunction "HSO/CSYNC_1") (pintype "passive"))
    )
    (net (code "66") (name "unconnected-(U1-NC1-Pad15)") (class "Default")
      (node (ref "U1") (pin "15") (pinfunction "NC1_15") (pintype "passive"))
    )
    (net (code "67") (name "unconnected-(U1-NC2-Pad16)") (class "Default")
      (node (ref "U1") (pin "16") (pinfunction "NC2_16") (pintype "passive"))
    )
    (net (code "68") (name "unconnected-(U1-NC3-Pad17)") (class "Default")
      (node (ref "U1") (pin "17") (pinfunction "NC3_17") (pintype "passive"))
    )
    (net (code "69") (name "unconnected-(U1-NC4-Pad20)") (class "Default")
      (node (ref "U1") (pin "20") (pinfunction "NC4_20") (pintype "passive"))
    )
    (net (code "70") (name "unconnected-(U1-NC5-Pad21)") (class "Default")
      (node (ref "U1") (pin "21") (pinfunction "NC5_21") (pintype "passive"))
    )
    (net (code "71") (name "unconnected-(U1-NC6-Pad22)") (class "Default")
      (node (ref "U1") (pin "22") (pinfunction "NC6_22") (pintype "passive"))
    )
    (net (code "72") (name "unconnected-(U1-NC7-Pad23)") (class "Default")
      (node (ref "U1") (pin "23") (pinfunction "NC7_23") (pintype "passive"))
    )
    (net (code "73") (name "unconnected-(U1-NC8-Pad40)") (class "Default")
      (node (ref "U1") (pin "40") (pinfunction "NC8_40") (pintype "passive"))
    )
    (net (code "74") (name "unconnected-(U1-NC9-Pad41)") (class "Default")
      (node (ref "U1") (pin "41") (pinfunction "NC9_41") (pintype "passive"))
    )
    (net (code "75") (name "unconnected-(U1-NC10-Pad42)") (class "Default")
      (node (ref "U1") (pin "42") (pinfunction "NC10_42") (pintype "passive"))
    )
    (net (code "76") (name "unconnected-(U1-NC11-Pad43)") (class "Default")
      (node (ref "U1") (pin "43") (pinfunction "NC11_43") (pintype "passive"))
    )
    (net (code "77") (name "unconnected-(U1-VSO{slash}CSYNC-Pad2)") (class "Default")
      (node (ref "U1") (pin "2") (pinfunction "VSO/CSYNC_2") (pintype "passive"))
    )
    (net (code "78") (name "unconnected-(U2-P0.4-Pad19)") (class "Default")
      (node (ref "U2") (pin "19") (pinfunction "P0.4_19") (pintype "passive"))
    )
    (net (code "79") (name "unconnected-(U2-P0.5-Pad18)") (class "Default")
      (node (ref "U2") (pin "18") (pinfunction "P0.5_18") (pintype "passive"))
    )
    (net (code "80") (name "unconnected-(U2-P0.6-Pad17)") (class "Default")
      (node (ref "U2") (pin "17") (pinfunction "P0.6_17") (pintype "passive"))
    )
    (net (code "81") (name "unconnected-(U2-P0.7-Pad16)") (class "Default")
      (node (ref "U2") (pin "16") (pinfunction "P0.7_16") (pintype "passive"))
    )
    (net (code "82") (name "unconnected-(U2-P1.2-Pad1)") (class "Default")
      (node (ref "U2") (pin "1") (pinfunction "P1.2_1") (pintype "passive"))
    )
    (net (code "83") (name "unconnected-(U2-P1.3-Pad2)") (class "Default")
      (node (ref "U2") (pin "2") (pinfunction "P1.3_2") (pintype "passive"))
    )
    (net (code "84") (name "unconnected-(U2-P1.4-Pad3)") (class "Default")
      (node (ref "U2") (pin "3") (pinfunction "P1.4_3") (pintype "passive"))
    )
    (net (code "85") (name "unconnected-(U2-P1.5-Pad4)") (class "Default")
      (node (ref "U2") (pin "4") (pinfunction "P1.5_4") (pintype "passive"))
    )
    (net (code "86") (name "unconnected-(U2-P2.4-Pad12)") (class "Default")
      (node (ref "U2") (pin "12") (pinfunction "P2.4_12") (pintype "passive"))
    )
    (net (code "87") (name "unconnected-(U2-P2.5-Pad13)") (class "Default")
      (node (ref "U2") (pin "13") (pinfunction "P2.5_13") (pintype "passive"))
    )
    (net (code "88") (name "unconnected-(U2-P3.2-Pad6)") (class "Default")
      (node (ref "U2") (pin "6") (pinfunction "P3.2_6") (pintype "passive"))
    )
    (net (code "89") (name "unconnected-(U2-Vss-Pad11)") (class "Default")
      (node (ref "U2") (pin "11") (pinfunction "Vss_11") (pintype "passive"))
    )
  )
)
